# PCBMINI3.net
KiCad netlist of a schematic drawn in EAGLE
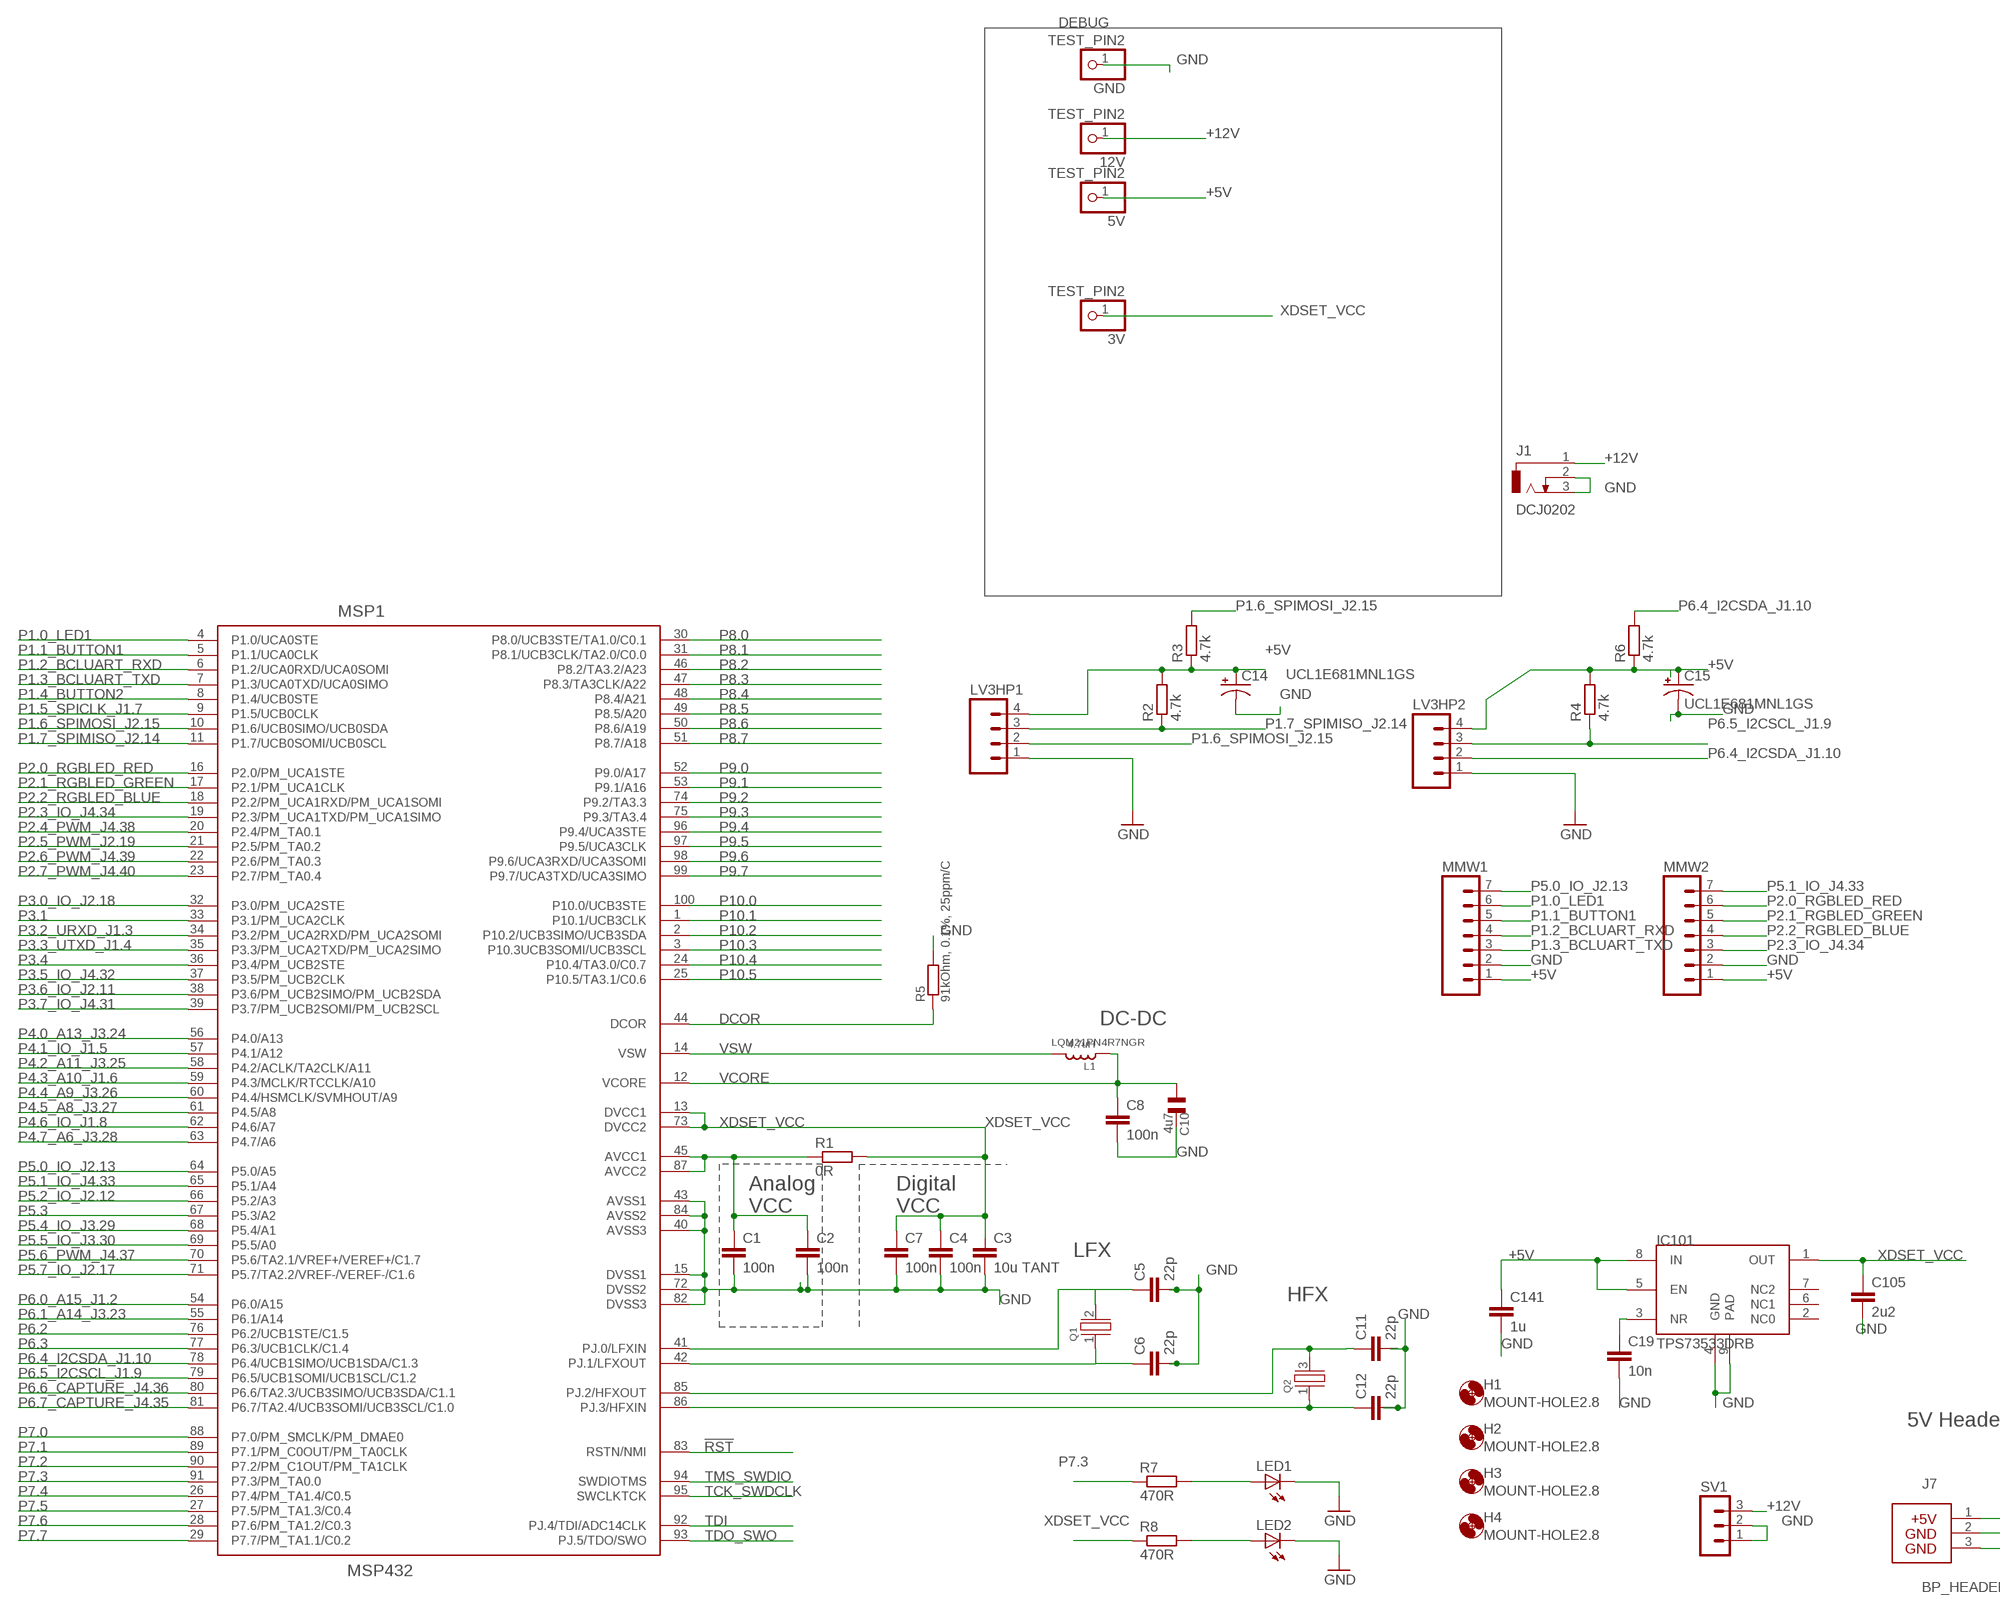
[diagram p0: schematic, sheet 1, part 1 of 2]
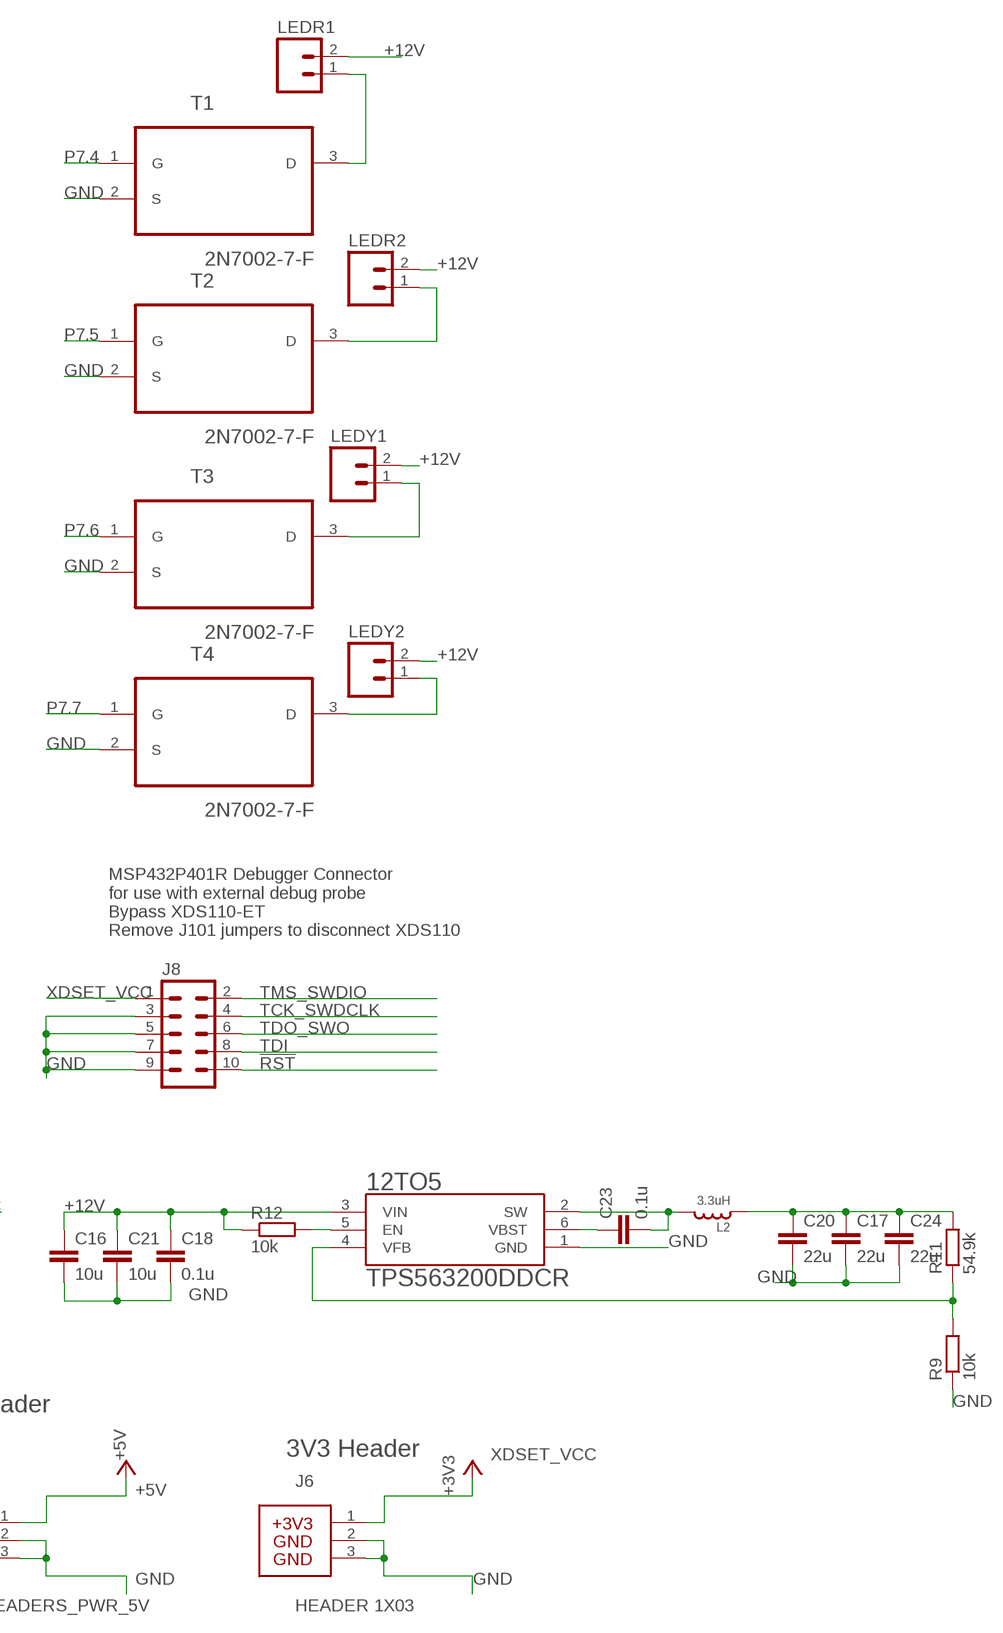
[diagram p1: schematic, sheet 1, part 2 of 2]

(export (version "E")
  (design (tool "Eeschema 10.0.6"))
  (components
    (comp (ref "3V")
      (value "TEST_PIN2")
      (footprint "eagle-import:1X01")
      (libsource (lib "eagle-import") (part "PINHD-1X1"))
    )
    (comp (ref "5V")
      (value "TEST_PIN2")
      (footprint "eagle-import:1X01")
      (libsource (lib "eagle-import") (part "PINHD-1X1"))
    )
    (comp (ref "12TO5")
      (value "TPS563200DDCR")
      (footprint "eagle-import:SOT95P280X110-6N")
      (fields (field (name "MF") "Texas Instruments"))
      (libsource (lib "eagle-import") (part "TPS563200DDCR"))
    )
    (comp (ref "12V")
      (value "TEST_PIN2")
      (footprint "eagle-import:1X01")
      (libsource (lib "eagle-import") (part "PINHD-1X1"))
    )
    (comp (ref "C1")
      (value "100n")
      (footprint "eagle-import:C0805")
      (libsource (lib "eagle-import") (part "C"))
    )
    (comp (ref "C2")
      (value "100n")
      (footprint "eagle-import:C0805")
      (libsource (lib "eagle-import") (part "C"))
    )
    (comp (ref "C3")
      (value "10u TANT")
      (footprint "eagle-import:C0805")
      (libsource (lib "eagle-import") (part "C"))
    )
    (comp (ref "C4")
      (value "100n")
      (footprint "eagle-import:C0805")
      (libsource (lib "eagle-import") (part "C"))
    )
    (comp (ref "C5")
      (value "22p")
      (footprint "eagle-import:C0805")
      (libsource (lib "eagle-import") (part "C"))
    )
    (comp (ref "C6")
      (value "22p")
      (footprint "eagle-import:C0805")
      (libsource (lib "eagle-import") (part "C"))
    )
    (comp (ref "C7")
      (value "100n")
      (footprint "eagle-import:C0805")
      (libsource (lib "eagle-import") (part "C"))
    )
    (comp (ref "C8")
      (value "100n")
      (footprint "eagle-import:C0805")
      (libsource (lib "eagle-import") (part "C"))
    )
    (comp (ref "C10")
      (value "4u7")
      (footprint "eagle-import:CSMD0805")
      (libsource (lib "eagle-import") (part "CSMD0805"))
    )
    (comp (ref "C11")
      (value "22p")
      (footprint "eagle-import:C0805")
      (libsource (lib "eagle-import") (part "C"))
    )
    (comp (ref "C12")
      (value "22p")
      (footprint "eagle-import:C0805")
      (libsource (lib "eagle-import") (part "C"))
    )
    (comp (ref "C14")
      (value "UCL1E681MNL1GS")
      (footprint "eagle-import:CAPAE1030X1350N")
      (fields (field (name "MF") "Nichicon"))
      (libsource (lib "eagle-import") (part "UCL1E681MNL1GS"))
    )
    (comp (ref "C15")
      (value "UCL1E681MNL1GS")
      (footprint "eagle-import:CAPAE1030X1350N")
      (fields (field (name "MF") "Nichicon"))
      (libsource (lib "eagle-import") (part "UCL1E681MNL1GS"))
    )
    (comp (ref "C16")
      (value "10u")
      (footprint "eagle-import:C0805")
      (libsource (lib "eagle-import") (part "C"))
    )
    (comp (ref "C17")
      (value "22u")
      (footprint "eagle-import:C0805")
      (libsource (lib "eagle-import") (part "C"))
    )
    (comp (ref "C18")
      (value "0.1u")
      (footprint "eagle-import:C0805")
      (libsource (lib "eagle-import") (part "C"))
    )
    (comp (ref "C19")
      (value "10n")
      (footprint "eagle-import:C0603")
      (libsource (lib "eagle-import") (part "C-EUC0603"))
    )
    (comp (ref "C20")
      (value "22u")
      (footprint "eagle-import:C0805")
      (libsource (lib "eagle-import") (part "C"))
    )
    (comp (ref "C21")
      (value "10u")
      (footprint "eagle-import:C0805")
      (libsource (lib "eagle-import") (part "C"))
    )
    (comp (ref "C23")
      (value "0.1u")
      (footprint "eagle-import:C0805")
      (libsource (lib "eagle-import") (part "C"))
    )
    (comp (ref "C24")
      (value "22u")
      (footprint "eagle-import:C0805")
      (libsource (lib "eagle-import") (part "C"))
    )
    (comp (ref "C105")
      (value "2u2")
      (footprint "eagle-import:C0603")
      (libsource (lib "eagle-import") (part "C-EUC0603"))
    )
    (comp (ref "C141")
      (value "1u")
      (footprint "eagle-import:C0603")
      (libsource (lib "eagle-import") (part "C-EUC0603"))
    )
    (comp (ref "GND")
      (value "TEST_PIN2")
      (footprint "eagle-import:1X01")
      (libsource (lib "eagle-import") (part "PINHD-1X1"))
    )
    (comp (ref "H1")
      (value "MOUNT-HOLE2.8")
      (footprint "eagle-import:2,8")
      (libsource (lib "eagle-import") (part "MOUNT-HOLE2.8"))
    )
    (comp (ref "H2")
      (value "MOUNT-HOLE2.8")
      (footprint "eagle-import:2,8")
      (libsource (lib "eagle-import") (part "MOUNT-HOLE2.8"))
    )
    (comp (ref "H3")
      (value "MOUNT-HOLE2.8")
      (footprint "eagle-import:2,8")
      (libsource (lib "eagle-import") (part "MOUNT-HOLE2.8"))
    )
    (comp (ref "H4")
      (value "MOUNT-HOLE2.8")
      (footprint "eagle-import:2,8")
      (libsource (lib "eagle-import") (part "MOUNT-HOLE2.8"))
    )
    (comp (ref "IC101")
      (value "TPS73533DRB")
      (footprint "eagle-import:SON8")
      (libsource (lib "eagle-import") (part "TPS73633DRB"))
    )
    (comp (ref "J1")
      (value "DCJ0202")
      (footprint "eagle-import:DCJ0202")
      (libsource (lib "eagle-import") (part "DCJ0202"))
    )
    (comp (ref "J6")
      (value "HEADER 1X03")
      (footprint "eagle-import:3PIN_PWR_3V3")
      (libsource (lib "eagle-import") (part "BP_HEADERS_PWR_3V3-TH100"))
    )
    (comp (ref "J7")
      (value "BP_HEADERS_PWR_5V")
      (footprint "eagle-import:3PIN_PWR_5V")
      (libsource (lib "eagle-import") (part "BP_HEADERS_PWR_5V"))
    )
    (comp (ref "J8")
      (value "DEBUG_ARM-10")
      (footprint "eagle-import:ARM-10")
      (libsource (lib "eagle-import") (part "DEBUG_ARM-10"))
    )
    (comp (ref "L1")
      (value "4.7uH")
      (footprint "eagle-import:0806")
      (libsource (lib "eagle-import") (part "LQM2MP_G0"))
    )
    (comp (ref "L2")
      (value "3.3uH")
      (footprint "eagle-import:0806")
      (libsource (lib "eagle-import") (part "LQM2MP_G0"))
    )
    (comp (ref "LED1")
      (value "LED_E")
      (footprint "eagle-import:LED_1206")
      (libsource (lib "eagle-import") (part "LED_E"))
    )
    (comp (ref "LED2")
      (value "LED_E")
      (footprint "eagle-import:LED_1206")
      (libsource (lib "eagle-import") (part "LED_E"))
    )
    (comp (ref "LEDR1")
      (value "MA02")
      (footprint "eagle-import:02PA")
      (libsource (lib "eagle-import") (part "MA02"))
    )
    (comp (ref "LEDR2")
      (value "MA02")
      (footprint "eagle-import:02PA")
      (libsource (lib "eagle-import") (part "MA02"))
    )
    (comp (ref "LEDY1")
      (value "MA02")
      (footprint "eagle-import:02PA")
      (libsource (lib "eagle-import") (part "MA02"))
    )
    (comp (ref "LEDY2")
      (value "MA02")
      (footprint "eagle-import:02PA")
      (libsource (lib "eagle-import") (part "MA02"))
    )
    (comp (ref "LV3HP1")
      (value "MA04")
      (footprint "eagle-import:04PA")
      (libsource (lib "eagle-import") (part "MA04"))
    )
    (comp (ref "LV3HP2")
      (value "MA04")
      (footprint "eagle-import:04PA")
      (libsource (lib "eagle-import") (part "MA04"))
    )
    (comp (ref "MMW1")
      (value "MA07")
      (footprint "eagle-import:07PA")
      (libsource (lib "eagle-import") (part "MA07"))
    )
    (comp (ref "MMW2")
      (value "MA07")
      (footprint "eagle-import:07PA")
      (libsource (lib "eagle-import") (part "MA07"))
    )
    (comp (ref "MSP1")
      (value "MSP432")
      (footprint "eagle-import:PZ100")
      (libsource (lib "eagle-import") (part "MSP432"))
    )
    (comp (ref "Q1")
      (value "CRYSTALLF_GENERAL")
      (footprint "eagle-import:LF_XTAL")
      (libsource (lib "eagle-import") (part "CRYSTALLF_GENERAL"))
    )
    (comp (ref "Q2")
      (value "CRYSTALEPSON_FA-238")
      (footprint "eagle-import:FA-238")
      (libsource (lib "eagle-import") (part "CRYSTALEPSON_FA-238"))
    )
    (comp (ref "R1")
      (value "0R")
      (footprint "eagle-import:R0805")
      (libsource (lib "eagle-import") (part "R"))
    )
    (comp (ref "R2")
      (value "4.7k")
      (footprint "eagle-import:R0805")
      (libsource (lib "eagle-import") (part "R"))
    )
    (comp (ref "R3")
      (value "4.7k")
      (footprint "eagle-import:R0805")
      (libsource (lib "eagle-import") (part "R"))
    )
    (comp (ref "R4")
      (value "4.7k")
      (footprint "eagle-import:R0805")
      (libsource (lib "eagle-import") (part "R"))
    )
    (comp (ref "R5")
      (value "91kOhm, 0.1%, 25ppm/C")
      (footprint "eagle-import:0805")
      (libsource (lib "eagle-import") (part "R_0805"))
    )
    (comp (ref "R6")
      (value "4.7k")
      (footprint "eagle-import:R0805")
      (libsource (lib "eagle-import") (part "R"))
    )
    (comp (ref "R7")
      (value "470R")
      (footprint "eagle-import:R0805")
      (libsource (lib "eagle-import") (part "R"))
    )
    (comp (ref "R8")
      (value "470R")
      (footprint "eagle-import:R0805")
      (libsource (lib "eagle-import") (part "R"))
    )
    (comp (ref "R9")
      (value "10k")
      (footprint "eagle-import:R0805")
      (libsource (lib "eagle-import") (part "R"))
    )
    (comp (ref "R11")
      (value "54.9k")
      (footprint "eagle-import:R0805")
      (libsource (lib "eagle-import") (part "R"))
    )
    (comp (ref "R12")
      (value "10k")
      (footprint "eagle-import:R0805")
      (libsource (lib "eagle-import") (part "R"))
    )
    (comp (ref "SV1")
      (value "MA03-1")
      (footprint "eagle-import:MA03-1")
      (libsource (lib "eagle-import") (part "MA03-1"))
    )
    (comp (ref "T1")
      (value "2N7002-7-F")
      (footprint "eagle-import:SOT103P240X110-3N")
      (fields (field (name "MF") "Diodes Inc."))
      (libsource (lib "eagle-import") (part "2N7002-7-F"))
    )
    (comp (ref "T2")
      (value "2N7002-7-F")
      (footprint "eagle-import:SOT103P240X110-3N")
      (fields (field (name "MF") "Diodes Inc."))
      (libsource (lib "eagle-import") (part "2N7002-7-F"))
    )
    (comp (ref "T3")
      (value "2N7002-7-F")
      (footprint "eagle-import:SOT103P240X110-3N")
      (fields (field (name "MF") "Diodes Inc."))
      (libsource (lib "eagle-import") (part "2N7002-7-F"))
    )
    (comp (ref "T4")
      (value "2N7002-7-F")
      (footprint "eagle-import:SOT103P240X110-3N")
      (fields (field (name "MF") "Diodes Inc."))
      (libsource (lib "eagle-import") (part "2N7002-7-F"))
    )
  )
  (nets
    (net (code "1") (name "+3V3") (class "Default")
      (node (ref "3V") (pin "1") (pinfunction "1_1") (pintype "passive"))
      (node (ref "C105") (pin "1") (pinfunction "1_1") (pintype "passive"))
      (node (ref "C3") (pin "1") (pinfunction "1_1") (pintype "passive"))
      (node (ref "C4") (pin "1") (pinfunction "1_1") (pintype "passive"))
      (node (ref "C7") (pin "1") (pinfunction "1_1") (pintype "passive"))
      (node (ref "IC101") (pin "1") (pinfunction "OUT_1") (pintype "bidirectional"))
      (node (ref "J6") (pin "1") (pinfunction "1_1") (pintype "bidirectional"))
      (node (ref "J8") (pin "1") (pinfunction "1_1") (pintype "passive"))
      (node (ref "MSP1") (pin "13") (pinfunction "DVCC1_13") (pintype "power_in"))
      (node (ref "MSP1") (pin "73") (pinfunction "DVCC2_73") (pintype "power_in"))
      (node (ref "R1") (pin "2") (pinfunction "2_2") (pintype "passive"))
      (node (ref "R8") (pin "1") (pinfunction "1_1") (pintype "passive"))
    )
    (net (code "2") (name "+5V") (class "Default")
      (node (ref "5V") (pin "1") (pinfunction "1_1") (pintype "passive"))
      (node (ref "C14") (pin "A") (pinfunction "+_A") (pintype "passive"))
      (node (ref "C141") (pin "1") (pinfunction "1_1") (pintype "passive"))
      (node (ref "C15") (pin "A") (pinfunction "+_A") (pintype "passive"))
      (node (ref "IC101") (pin "5") (pinfunction "EN_5") (pintype "bidirectional"))
      (node (ref "IC101") (pin "8") (pinfunction "IN_8") (pintype "bidirectional"))
      (node (ref "J7") (pin "1") (pinfunction "1_1") (pintype "bidirectional"))
      (node (ref "LV3HP1") (pin "4") (pinfunction "4_4") (pintype "passive"))
      (node (ref "LV3HP2") (pin "4") (pinfunction "4_4") (pintype "passive"))
      (node (ref "MMW1") (pin "1") (pinfunction "1_1") (pintype "passive"))
      (node (ref "MMW2") (pin "1") (pinfunction "1_1") (pintype "passive"))
      (node (ref "R2") (pin "2") (pinfunction "2_2") (pintype "passive"))
      (node (ref "R3") (pin "1") (pinfunction "1_1") (pintype "passive"))
      (node (ref "R4") (pin "2") (pinfunction "2_2") (pintype "passive"))
      (node (ref "R6") (pin "1") (pinfunction "1_1") (pintype "passive"))
    )
    (net (code "3") (name "/+12V") (class "Default")
      (node (ref "12TO5") (pin "3") (pinfunction "VIN_3") (pintype "input"))
      (node (ref "12V") (pin "1") (pinfunction "1_1") (pintype "passive"))
      (node (ref "C16") (pin "1") (pinfunction "1_1") (pintype "passive"))
      (node (ref "C18") (pin "1") (pinfunction "1_1") (pintype "passive"))
      (node (ref "C21") (pin "1") (pinfunction "1_1") (pintype "passive"))
      (node (ref "J1") (pin "1") (pinfunction "1_1") (pintype "passive"))
      (node (ref "LEDR1") (pin "2") (pinfunction "2_2") (pintype "passive"))
      (node (ref "LEDR2") (pin "2") (pinfunction "2_2") (pintype "passive"))
      (node (ref "LEDY1") (pin "2") (pinfunction "2_2") (pintype "passive"))
      (node (ref "LEDY2") (pin "2") (pinfunction "2_2") (pintype "passive"))
      (node (ref "R12") (pin "1") (pinfunction "1_1") (pintype "passive"))
      (node (ref "SV1") (pin "3") (pinfunction "3_3") (pintype "passive"))
    )
    (net (code "4") (name "/DCOR") (class "Default")
      (node (ref "MSP1") (pin "44") (pinfunction "DCOR_44") (pintype "power_in"))
      (node (ref "R5") (pin "1") (pinfunction "1_1") (pintype "passive"))
    )
    (net (code "5") (name "/P1.0_LED1") (class "Default")
      (node (ref "MMW1") (pin "6") (pinfunction "6_6") (pintype "passive"))
      (node (ref "MSP1") (pin "4") (pinfunction "P1.0/UCA0STE_4") (pintype "power_in"))
    )
    (net (code "6") (name "/P1.1_BUTTON1") (class "Default")
      (node (ref "MMW1") (pin "5") (pinfunction "5_5") (pintype "passive"))
      (node (ref "MSP1") (pin "5") (pinfunction "P1.1/UCA0CLK_5") (pintype "power_in"))
    )
    (net (code "7") (name "/P1.2_BCLUART_RXD") (class "Default")
      (node (ref "MMW1") (pin "4") (pinfunction "4_4") (pintype "passive"))
      (node (ref "MSP1") (pin "6") (pinfunction "P1.2/UCA0RXD/UCA0SOMI_6") (pintype "power_in"))
    )
    (net (code "8") (name "/P1.3_BCLUART_TXD") (class "Default")
      (node (ref "MMW1") (pin "3") (pinfunction "3_3") (pintype "passive"))
      (node (ref "MSP1") (pin "7") (pinfunction "P1.3/UCA0TXD/UCA0SIMO_7") (pintype "power_in"))
    )
    (net (code "9") (name "/P1.4_BUTTON2") (class "Default")
      (node (ref "MSP1") (pin "8") (pinfunction "P1.4/UCB0STE_8") (pintype "power_in"))
    )
    (net (code "10") (name "/P1.5_SPICLK_J1.7") (class "Default")
      (node (ref "MSP1") (pin "9") (pinfunction "P1.5/UCB0CLK_9") (pintype "power_in"))
    )
    (net (code "11") (name "/P1.6_SPIMOSI_J2.15") (class "Default")
      (node (ref "LV3HP1") (pin "2") (pinfunction "2_2") (pintype "passive"))
      (node (ref "MSP1") (pin "10") (pinfunction "P1.6/UCB0SIMO/UCB0SDA_10") (pintype "power_in"))
      (node (ref "R3") (pin "2") (pinfunction "2_2") (pintype "passive"))
    )
    (net (code "12") (name "/P1.7_SPIMISO_J2.14") (class "Default")
      (node (ref "LV3HP1") (pin "3") (pinfunction "3_3") (pintype "passive"))
      (node (ref "MSP1") (pin "11") (pinfunction "P1.7/UCB0SOMI/UCB0SCL_11") (pintype "power_in"))
      (node (ref "R2") (pin "1") (pinfunction "1_1") (pintype "passive"))
    )
    (net (code "13") (name "/P2.0_RGBLED_RED") (class "Default")
      (node (ref "MMW2") (pin "6") (pinfunction "6_6") (pintype "passive"))
      (node (ref "MSP1") (pin "16") (pinfunction "P2.0/PM_UCA1STE_16") (pintype "power_in"))
    )
    (net (code "14") (name "/P2.1_RGBLED_GREEN") (class "Default")
      (node (ref "MMW2") (pin "5") (pinfunction "5_5") (pintype "passive"))
      (node (ref "MSP1") (pin "17") (pinfunction "P2.1/PM_UCA1CLK_17") (pintype "power_in"))
    )
    (net (code "15") (name "/P2.2_RGBLED_BLUE") (class "Default")
      (node (ref "MMW2") (pin "4") (pinfunction "4_4") (pintype "passive"))
      (node (ref "MSP1") (pin "18") (pinfunction "P2.2/PM_UCA1RXD/PM_UCA1SOMI_18") (pintype "power_in"))
    )
    (net (code "16") (name "/P2.3_IO_J4.34") (class "Default")
      (node (ref "MMW2") (pin "3") (pinfunction "3_3") (pintype "passive"))
      (node (ref "MSP1") (pin "19") (pinfunction "P2.3/PM_UCA1TXD/PM_UCA1SIMO_19") (pintype "power_in"))
    )
    (net (code "17") (name "/P2.4_PWM_J4.38") (class "Default")
      (node (ref "MSP1") (pin "20") (pinfunction "P2.4/PM_TA0.1_20") (pintype "power_in"))
    )
    (net (code "18") (name "/P2.5_PWM_J2.19") (class "Default")
      (node (ref "MSP1") (pin "21") (pinfunction "P2.5/PM_TA0.2_21") (pintype "power_in"))
    )
    (net (code "19") (name "/P2.6_PWM_J4.39") (class "Default")
      (node (ref "MSP1") (pin "22") (pinfunction "P2.6/PM_TA0.3_22") (pintype "power_in"))
    )
    (net (code "20") (name "/P2.7_PWM_J4.40") (class "Default")
      (node (ref "MSP1") (pin "23") (pinfunction "P2.7/PM_TA0.4_23") (pintype "power_in"))
    )
    (net (code "21") (name "/P3.0_IO_J2.18") (class "Default")
      (node (ref "MSP1") (pin "32") (pinfunction "P3.0/PM_UCA2STE_32") (pintype "power_in"))
    )
    (net (code "22") (name "/P3.1") (class "Default")
      (node (ref "MSP1") (pin "33") (pinfunction "P3.1/PM_UCA2CLK_33") (pintype "power_in"))
    )
    (net (code "23") (name "/P3.2_URXD_J1.3") (class "Default")
      (node (ref "MSP1") (pin "34") (pinfunction "P3.2/PM_UCA2RXD/PM_UCA2SOMI_34") (pintype "power_in"))
    )
    (net (code "24") (name "/P3.3_UTXD_J1.4") (class "Default")
      (node (ref "MSP1") (pin "35") (pinfunction "P3.3/PM_UCA2TXD/PM_UCA2SIMO_35") (pintype "power_in"))
    )
    (net (code "25") (name "/P3.4") (class "Default")
      (node (ref "MSP1") (pin "36") (pinfunction "P3.4/PM_UCB2STE_36") (pintype "power_in"))
    )
    (net (code "26") (name "/P3.5_IO_J4.32") (class "Default")
      (node (ref "MSP1") (pin "37") (pinfunction "P3.5/PM_UCB2CLK_37") (pintype "power_in"))
    )
    (net (code "27") (name "/P3.6_IO_J2.11") (class "Default")
      (node (ref "MSP1") (pin "38") (pinfunction "P3.6/PM_UCB2SIMO/PM_UCB2SDA_38") (pintype "power_in"))
    )
    (net (code "28") (name "/P3.7_IO_J4.31") (class "Default")
      (node (ref "MSP1") (pin "39") (pinfunction "P3.7/PM_UCB2SOMI/PM_UCB2SCL_39") (pintype "power_in"))
    )
    (net (code "29") (name "/P4.0_A13_J3.24") (class "Default")
      (node (ref "MSP1") (pin "56") (pinfunction "P4.0/A13_56") (pintype "power_in"))
    )
    (net (code "30") (name "/P4.1_IO_J1.5") (class "Default")
      (node (ref "MSP1") (pin "57") (pinfunction "P4.1/A12_57") (pintype "power_in"))
    )
    (net (code "31") (name "/P4.2_A11_J3.25") (class "Default")
      (node (ref "MSP1") (pin "58") (pinfunction "P4.2/ACLK/TA2CLK/A11_58") (pintype "power_in"))
    )
    (net (code "32") (name "/P4.3_A10_J1.6") (class "Default")
      (node (ref "MSP1") (pin "59") (pinfunction "P4.3/MCLK/RTCCLK/A10_59") (pintype "power_in"))
    )
    (net (code "33") (name "/P4.4_A9_J3.26") (class "Default")
      (node (ref "MSP1") (pin "60") (pinfunction "P4.4/HSMCLK/SVMHOUT/A9_60") (pintype "power_in"))
    )
    (net (code "34") (name "/P4.5_A8_J3.27") (class "Default")
      (node (ref "MSP1") (pin "61") (pinfunction "P4.5/A8_61") (pintype "power_in"))
    )
    (net (code "35") (name "/P4.6_IO_J1.8") (class "Default")
      (node (ref "MSP1") (pin "62") (pinfunction "P4.6/A7_62") (pintype "power_in"))
    )
    (net (code "36") (name "/P4.7_A6_J3.28") (class "Default")
      (node (ref "MSP1") (pin "63") (pinfunction "P4.7/A6_63") (pintype "power_in"))
    )
    (net (code "37") (name "/P5.0_IO_J2.13") (class "Default")
      (node (ref "MMW1") (pin "7") (pinfunction "7_7") (pintype "passive"))
      (node (ref "MSP1") (pin "64") (pinfunction "P5.0/A5_64") (pintype "power_in"))
    )
    (net (code "38") (name "/P5.1_IO_J4.33") (class "Default")
      (node (ref "MMW2") (pin "7") (pinfunction "7_7") (pintype "passive"))
      (node (ref "MSP1") (pin "65") (pinfunction "P5.1/A4_65") (pintype "power_in"))
    )
    (net (code "39") (name "/P5.2_IO_J2.12") (class "Default")
      (node (ref "MSP1") (pin "66") (pinfunction "P5.2/A3_66") (pintype "power_in"))
    )
    (net (code "40") (name "/P5.3") (class "Default")
      (node (ref "MSP1") (pin "67") (pinfunction "P5.3/A2_67") (pintype "power_in"))
    )
    (net (code "41") (name "/P5.4_IO_J3.29") (class "Default")
      (node (ref "MSP1") (pin "68") (pinfunction "P5.4/A1_68") (pintype "power_in"))
    )
    (net (code "42") (name "/P5.5_IO_J3.30") (class "Default")
      (node (ref "MSP1") (pin "69") (pinfunction "P5.5/A0_69") (pintype "power_in"))
    )
    (net (code "43") (name "/P5.6_PWM_J4.37") (class "Default")
      (node (ref "MSP1") (pin "70") (pinfunction "P5.6/TA2.1/VREF+/VEREF+/C1.7_70") (pintype "power_in"))
    )
    (net (code "44") (name "/P5.7_IO_J2.17") (class "Default")
      (node (ref "MSP1") (pin "71") (pinfunction "P5.7/TA2.2/VREF-/VEREF-/C1.6_71") (pintype "power_in"))
    )
    (net (code "45") (name "/P6.0_A15_J1.2") (class "Default")
      (node (ref "MSP1") (pin "54") (pinfunction "P6.0/A15_54") (pintype "power_in"))
    )
    (net (code "46") (name "/P6.1_A14_J3.23") (class "Default")
      (node (ref "MSP1") (pin "55") (pinfunction "P6.1/A14_55") (pintype "power_in"))
    )
    (net (code "47") (name "/P6.2") (class "Default")
      (node (ref "MSP1") (pin "76") (pinfunction "P6.2/UCB1STE/C1.5_76") (pintype "power_in"))
    )
    (net (code "48") (name "/P6.3") (class "Default")
      (node (ref "MSP1") (pin "77") (pinfunction "P6.3/UCB1CLK/C1.4_77") (pintype "power_in"))
    )
    (net (code "49") (name "/P6.4_I2CSDA_J1.10") (class "Default")
      (node (ref "LV3HP2") (pin "2") (pinfunction "2_2") (pintype "passive"))
      (node (ref "MSP1") (pin "78") (pinfunction "P6.4/UCB1SIMO/UCB1SDA/C1.3_78") (pintype "power_in"))
      (node (ref "R6") (pin "2") (pinfunction "2_2") (pintype "passive"))
    )
    (net (code "50") (name "/P6.5_I2CSCL_J1.9") (class "Default")
      (node (ref "LV3HP2") (pin "3") (pinfunction "3_3") (pintype "passive"))
      (node (ref "MSP1") (pin "79") (pinfunction "P6.5/UCB1SOMI/UCB1SCL/C1.2_79") (pintype "power_in"))
      (node (ref "R4") (pin "1") (pinfunction "1_1") (pintype "passive"))
    )
    (net (code "51") (name "/P6.6_CAPTURE_J4.36") (class "Default")
      (node (ref "MSP1") (pin "80") (pinfunction "P6.6/TA2.3/UCB3SIMO/UCB3SDA/C1.1_80") (pintype "power_in"))
    )
    (net (code "52") (name "/P6.7_CAPTURE_J4.35") (class "Default")
      (node (ref "MSP1") (pin "81") (pinfunction "P6.7/TA2.4/UCB3SOMI/UCB3SCL/C1.0_81") (pintype "power_in"))
    )
    (net (code "53") (name "/P7.0") (class "Default")
      (node (ref "MSP1") (pin "88") (pinfunction "P7.0/PM_SMCLK/PM_DMAE0_88") (pintype "power_in"))
    )
    (net (code "54") (name "/P7.1") (class "Default")
      (node (ref "MSP1") (pin "89") (pinfunction "P7.1/PM_C0OUT/PM_TA0CLK_89") (pintype "power_in"))
    )
    (net (code "55") (name "/P7.2") (class "Default")
      (node (ref "MSP1") (pin "90") (pinfunction "P7.2/PM_C1OUT/PM_TA1CLK_90") (pintype "power_in"))
    )
    (net (code "56") (name "/P7.3") (class "Default")
      (node (ref "MSP1") (pin "91") (pinfunction "P7.3/PM_TA0.0_91") (pintype "power_in"))
      (node (ref "R7") (pin "1") (pinfunction "1_1") (pintype "passive"))
    )
    (net (code "57") (name "/P7.4") (class "Default")
      (node (ref "MSP1") (pin "26") (pinfunction "P7.4/PM_TA1.4/C0.5_26") (pintype "power_in"))
      (node (ref "T1") (pin "1") (pinfunction "G_1") (pintype "input"))
    )
    (net (code "58") (name "/P7.5") (class "Default")
      (node (ref "MSP1") (pin "27") (pinfunction "P7.5/PM_TA1.3/C0.4_27") (pintype "power_in"))
      (node (ref "T2") (pin "1") (pinfunction "G_1") (pintype "input"))
    )
    (net (code "59") (name "/P7.6") (class "Default")
      (node (ref "MSP1") (pin "28") (pinfunction "P7.6/PM_TA1.2/C0.3_28") (pintype "power_in"))
      (node (ref "T3") (pin "1") (pinfunction "G_1") (pintype "input"))
    )
    (net (code "60") (name "/P7.7") (class "Default")
      (node (ref "MSP1") (pin "29") (pinfunction "P7.7/PM_TA1.1/C0.2_29") (pintype "power_in"))
      (node (ref "T4") (pin "1") (pinfunction "G_1") (pintype "input"))
    )
    (net (code "61") (name "/P8.0") (class "Default")
      (node (ref "MSP1") (pin "30") (pinfunction "P8.0/UCB3STE/TA1.0/C0.1_30") (pintype "power_in"))
    )
    (net (code "62") (name "/P8.1") (class "Default")
      (node (ref "MSP1") (pin "31") (pinfunction "P8.1/UCB3CLK/TA2.0/C0.0_31") (pintype "power_in"))
    )
    (net (code "63") (name "/P8.2") (class "Default")
      (node (ref "MSP1") (pin "46") (pinfunction "P8.2/TA3.2/A23_46") (pintype "power_in"))
    )
    (net (code "64") (name "/P8.3") (class "Default")
      (node (ref "MSP1") (pin "47") (pinfunction "P8.3/TA3CLK/A22_47") (pintype "power_in"))
    )
    (net (code "65") (name "/P8.4") (class "Default")
      (node (ref "MSP1") (pin "48") (pinfunction "P8.4/A21_48") (pintype "power_in"))
    )
    (net (code "66") (name "/P8.5") (class "Default")
      (node (ref "MSP1") (pin "49") (pinfunction "P8.5/A20_49") (pintype "power_in"))
    )
    (net (code "67") (name "/P8.6") (class "Default")
      (node (ref "MSP1") (pin "50") (pinfunction "P8.6/A19_50") (pintype "power_in"))
    )
    (net (code "68") (name "/P8.7") (class "Default")
      (node (ref "MSP1") (pin "51") (pinfunction "P8.7/A18_51") (pintype "power_in"))
    )
    (net (code "69") (name "/P9.0") (class "Default")
      (node (ref "MSP1") (pin "52") (pinfunction "P9.0/A17_52") (pintype "power_in"))
    )
    (net (code "70") (name "/P9.1") (class "Default")
      (node (ref "MSP1") (pin "53") (pinfunction "P9.1/A16_53") (pintype "power_in"))
    )
    (net (code "71") (name "/P9.2") (class "Default")
      (node (ref "MSP1") (pin "74") (pinfunction "P9.2/TA3.3_74") (pintype "power_in"))
    )
    (net (code "72") (name "/P9.3") (class "Default")
      (node (ref "MSP1") (pin "75") (pinfunction "P9.3/TA3.4_75") (pintype "power_in"))
    )
    (net (code "73") (name "/P9.4") (class "Default")
      (node (ref "MSP1") (pin "96") (pinfunction "P9.4/UCA3STE_96") (pintype "power_in"))
    )
    (net (code "74") (name "/P9.5") (class "Default")
      (node (ref "MSP1") (pin "97") (pinfunction "P9.5/UCA3CLK_97") (pintype "power_in"))
    )
    (net (code "75") (name "/P9.6") (class "Default")
      (node (ref "MSP1") (pin "98") (pinfunction "P9.6/UCA3RXD/UCA3SOMI_98") (pintype "power_in"))
    )
    (net (code "76") (name "/P9.7") (class "Default")
      (node (ref "MSP1") (pin "99") (pinfunction "P9.7/UCA3TXD/UCA3SIMO_99") (pintype "power_in"))
    )
    (net (code "77") (name "/P10.0") (class "Default")
      (node (ref "MSP1") (pin "100") (pinfunction "P10.0/UCB3STE_100") (pintype "power_in"))
    )
    (net (code "78") (name "/P10.1") (class "Default")
      (node (ref "MSP1") (pin "1") (pinfunction "P10.1/UCB3CLK_1") (pintype "power_in"))
    )
    (net (code "79") (name "/P10.2") (class "Default")
      (node (ref "MSP1") (pin "2") (pinfunction "P10.2/UCB3SIMO/UCB3SDA_2") (pintype "power_in"))
    )
    (net (code "80") (name "/P10.3") (class "Default")
      (node (ref "MSP1") (pin "3") (pinfunction "P10.3UCB3SOMI/UCB3SCL_3") (pintype "power_in"))
    )
    (net (code "81") (name "/P10.4") (class "Default")
      (node (ref "MSP1") (pin "24") (pinfunction "P10.4/TA3.0/C0.7_24") (pintype "power_in"))
    )
    (net (code "82") (name "/P10.5") (class "Default")
      (node (ref "MSP1") (pin "25") (pinfunction "P10.5/TA3.1/C0.6_25") (pintype "power_in"))
    )
    (net (code "83") (name "/TCK_SWDCLK") (class "Default")
      (node (ref "J8") (pin "4") (pinfunction "4_4") (pintype "passive"))
      (node (ref "MSP1") (pin "95") (pinfunction "SWCLKTCK_95") (pintype "power_in"))
    )
    (net (code "84") (name "/TDI") (class "Default")
      (node (ref "J8") (pin "8") (pinfunction "8_8") (pintype "passive"))
      (node (ref "MSP1") (pin "92") (pinfunction "PJ.4/TDI/ADC14CLK_92") (pintype "power_in"))
    )
    (net (code "85") (name "/TDO_SWO") (class "Default")
      (node (ref "J8") (pin "6") (pinfunction "6_6") (pintype "passive"))
      (node (ref "MSP1") (pin "93") (pinfunction "PJ.5/TDO/SWO_93") (pintype "power_in"))
    )
    (net (code "86") (name "/TMS_SWDIO") (class "Default")
      (node (ref "J8") (pin "2") (pinfunction "2_2") (pintype "passive"))
      (node (ref "MSP1") (pin "94") (pinfunction "SWDIOTMS_94") (pintype "power_in"))
    )
    (net (code "87") (name "/VCORE") (class "Default")
      (node (ref "C10") (pin "1") (pinfunction "1_1") (pintype "passive"))
      (node (ref "C8") (pin "1") (pinfunction "1_1") (pintype "passive"))
      (node (ref "L1") (pin "1") (pinfunction "1_1") (pintype "passive"))
      (node (ref "MSP1") (pin "12") (pinfunction "VCORE_12") (pintype "power_in"))
    )
    (net (code "88") (name "/VSW") (class "Default")
      (node (ref "L1") (pin "2") (pinfunction "2_2") (pintype "passive"))
      (node (ref "MSP1") (pin "14") (pinfunction "VSW_14") (pintype "power_in"))
    )
    (net (code "89") (name "/~{RST}") (class "Default")
      (node (ref "J8") (pin "10") (pinfunction "10_10") (pintype "passive"))
      (node (ref "MSP1") (pin "83") (pinfunction "RSTN/NMI_83") (pintype "power_in"))
    )
    (net (code "90") (name "GND") (class "Default")
      (node (ref "12TO5") (pin "1") (pinfunction "GND_1") (pintype "power_in"))
      (node (ref "C1") (pin "2") (pinfunction "2_2") (pintype "passive"))
      (node (ref "C10") (pin "2") (pinfunction "2_2") (pintype "passive"))
      (node (ref "C105") (pin "2") (pinfunction "2_2") (pintype "passive"))
      (node (ref "C11") (pin "2") (pinfunction "2_2") (pintype "passive"))
      (node (ref "C12") (pin "2") (pinfunction "2_2") (pintype "passive"))
      (node (ref "C14") (pin "C") (pinfunction "-_C") (pintype "passive"))
      (node (ref "C141") (pin "2") (pinfunction "2_2") (pintype "passive"))
      (node (ref "C15") (pin "C") (pinfunction "-_C") (pintype "passive"))
      (node (ref "C16") (pin "2") (pinfunction "2_2") (pintype "passive"))
      (node (ref "C17") (pin "2") (pinfunction "2_2") (pintype "passive"))
      (node (ref "C18") (pin "2") (pinfunction "2_2") (pintype "passive"))
      (node (ref "C19") (pin "2") (pinfunction "2_2") (pintype "passive"))
      (node (ref "C2") (pin "2") (pinfunction "2_2") (pintype "passive"))
      (node (ref "C20") (pin "2") (pinfunction "2_2") (pintype "passive"))
      (node (ref "C21") (pin "2") (pinfunction "2_2") (pintype "passive"))
      (node (ref "C24") (pin "2") (pinfunction "2_2") (pintype "passive"))
      (node (ref "C3") (pin "2") (pinfunction "2_2") (pintype "passive"))
      (node (ref "C4") (pin "2") (pinfunction "2_2") (pintype "passive"))
      (node (ref "C5") (pin "2") (pinfunction "2_2") (pintype "passive"))
      (node (ref "C6") (pin "2") (pinfunction "2_2") (pintype "passive"))
      (node (ref "C7") (pin "2") (pinfunction "2_2") (pintype "passive"))
      (node (ref "C8") (pin "2") (pinfunction "2_2") (pintype "passive"))
      (node (ref "GND") (pin "1") (pinfunction "1_1") (pintype "passive"))
      (node (ref "IC101") (pin "4") (pinfunction "GND_4") (pintype "bidirectional"))
      (node (ref "IC101") (pin "9") (pinfunction "PAD_9") (pintype "bidirectional"))
      (node (ref "J1") (pin "2") (pinfunction "2_2") (pintype "passive"))
      (node (ref "J1") (pin "3") (pinfunction "3_3") (pintype "passive"))
      (node (ref "J6") (pin "2") (pinfunction "2_2") (pintype "bidirectional"))
      (node (ref "J6") (pin "3") (pinfunction "3_3") (pintype "bidirectional"))
      (node (ref "J7") (pin "2") (pinfunction "2_2") (pintype "bidirectional"))
      (node (ref "J7") (pin "3") (pinfunction "3_3") (pintype "bidirectional"))
      (node (ref "J8") (pin "3") (pinfunction "3_3") (pintype "passive"))
      (node (ref "J8") (pin "5") (pinfunction "5_5") (pintype "passive"))
      (node (ref "J8") (pin "7") (pinfunction "7_7") (pintype "passive"))
      (node (ref "J8") (pin "9") (pinfunction "9_9") (pintype "passive"))
      (node (ref "LED1") (pin "C") (pinfunction "C_C") (pintype "passive"))
      (node (ref "LED2") (pin "C") (pinfunction "C_C") (pintype "passive"))
      (node (ref "LV3HP1") (pin "1") (pinfunction "1_1") (pintype "passive"))
      (node (ref "LV3HP2") (pin "1") (pinfunction "1_1") (pintype "passive"))
      (node (ref "MMW1") (pin "2") (pinfunction "2_2") (pintype "passive"))
      (node (ref "MMW2") (pin "2") (pinfunction "2_2") (pintype "passive"))
      (node (ref "MSP1") (pin "15") (pinfunction "DVSS1_15") (pintype "power_in"))
      (node (ref "MSP1") (pin "40") (pinfunction "AVSS3_40") (pintype "power_in"))
      (node (ref "MSP1") (pin "43") (pinfunction "AVSS1_43") (pintype "power_in"))
      (node (ref "MSP1") (pin "72") (pinfunction "DVSS2_72") (pintype "power_in"))
      (node (ref "MSP1") (pin "82") (pinfunction "DVSS3_82") (pintype "power_in"))
      (node (ref "MSP1") (pin "84") (pinfunction "AVSS2_84") (pintype "power_in"))
      (node (ref "R5") (pin "2") (pinfunction "2_2") (pintype "passive"))
      (node (ref "R9") (pin "1") (pinfunction "1_1") (pintype "passive"))
      (node (ref "SV1") (pin "1") (pinfunction "1_1") (pintype "passive"))
      (node (ref "SV1") (pin "2") (pinfunction "2_2") (pintype "passive"))
      (node (ref "T1") (pin "2") (pinfunction "S_2") (pintype "passive"))
      (node (ref "T2") (pin "2") (pinfunction "S_2") (pintype "passive"))
      (node (ref "T3") (pin "2") (pinfunction "S_2") (pintype "passive"))
      (node (ref "T4") (pin "2") (pinfunction "S_2") (pintype "passive"))
    )
    (net (code "91") (name "Net-(12TO5-EN)") (class "Default")
      (node (ref "12TO5") (pin "5") (pinfunction "EN_5") (pintype "input"))
      (node (ref "R12") (pin "2") (pinfunction "2_2") (pintype "passive"))
    )
    (net (code "92") (name "Net-(12TO5-SW)") (class "Default")
      (node (ref "12TO5") (pin "2") (pinfunction "SW_2") (pintype "passive"))
      (node (ref "C23") (pin "2") (pinfunction "2_2") (pintype "passive"))
      (node (ref "L2") (pin "2") (pinfunction "2_2") (pintype "passive"))
    )
    (net (code "93") (name "Net-(12TO5-VBST)") (class "Default")
      (node (ref "12TO5") (pin "6") (pinfunction "VBST_6") (pintype "passive"))
      (node (ref "C23") (pin "1") (pinfunction "1_1") (pintype "passive"))
    )
    (net (code "94") (name "Net-(12TO5-VFB)") (class "Default")
      (node (ref "12TO5") (pin "4") (pinfunction "VFB_4") (pintype "input"))
      (node (ref "R11") (pin "1") (pinfunction "1_1") (pintype "passive"))
      (node (ref "R9") (pin "2") (pinfunction "2_2") (pintype "passive"))
    )
    (net (code "95") (name "Net-(C17-Pad1)") (class "Default")
      (node (ref "C17") (pin "1") (pinfunction "1_1") (pintype "passive"))
      (node (ref "C20") (pin "1") (pinfunction "1_1") (pintype "passive"))
      (node (ref "C24") (pin "1") (pinfunction "1_1") (pintype "passive"))
      (node (ref "L2") (pin "1") (pinfunction "1_1") (pintype "passive"))
      (node (ref "R11") (pin "2") (pinfunction "2_2") (pintype "passive"))
    )
    (net (code "96") (name "Net-(IC101-NR)") (class "Default")
      (node (ref "C19") (pin "1") (pinfunction "1_1") (pintype "passive"))
      (node (ref "IC101") (pin "3") (pinfunction "NR_3") (pintype "bidirectional"))
    )
    (net (code "97") (name "Net-(LED1-PadA)") (class "Default")
      (node (ref "LED1") (pin "A") (pinfunction "A_A") (pintype "passive"))
      (node (ref "R7") (pin "2") (pinfunction "2_2") (pintype "passive"))
    )
    (net (code "98") (name "Net-(LED2-PadA)") (class "Default")
      (node (ref "LED2") (pin "A") (pinfunction "A_A") (pintype "passive"))
      (node (ref "R8") (pin "2") (pinfunction "2_2") (pintype "passive"))
    )
    (net (code "99") (name "Net-(MSP1-AVCC1)") (class "Default")
      (node (ref "C1") (pin "1") (pinfunction "1_1") (pintype "passive"))
      (node (ref "C2") (pin "1") (pinfunction "1_1") (pintype "passive"))
      (node (ref "MSP1") (pin "45") (pinfunction "AVCC1_45") (pintype "power_in"))
      (node (ref "MSP1") (pin "87") (pinfunction "AVCC2_87") (pintype "power_in"))
      (node (ref "R1") (pin "1") (pinfunction "1_1") (pintype "passive"))
    )
    (net (code "100") (name "Net-(MSP1-PJ.0{slash}LFXIN)") (class "Default")
      (node (ref "C5") (pin "1") (pinfunction "1_1") (pintype "passive"))
      (node (ref "MSP1") (pin "41") (pinfunction "PJ.0/LFXIN_41") (pintype "power_in"))
      (node (ref "Q1") (pin "2") (pinfunction "2_2") (pintype "passive"))
    )
    (net (code "101") (name "Net-(MSP1-PJ.1{slash}LFXOUT)") (class "Default")
      (node (ref "C6") (pin "1") (pinfunction "1_1") (pintype "passive"))
      (node (ref "MSP1") (pin "42") (pinfunction "PJ.1/LFXOUT_42") (pintype "power_in"))
      (node (ref "Q1") (pin "1") (pinfunction "1_1") (pintype "passive"))
    )
    (net (code "102") (name "Net-(MSP1-PJ.2{slash}HFXOUT)") (class "Default")
      (node (ref "C11") (pin "1") (pinfunction "1_1") (pintype "passive"))
      (node (ref "MSP1") (pin "85") (pinfunction "PJ.2/HFXOUT_85") (pintype "power_in"))
      (node (ref "Q2") (pin "3") (pinfunction "2_3") (pintype "passive"))
    )
    (net (code "103") (name "Net-(MSP1-PJ.3{slash}HFXIN)") (class "Default")
      (node (ref "C12") (pin "1") (pinfunction "1_1") (pintype "passive"))
      (node (ref "MSP1") (pin "86") (pinfunction "PJ.3/HFXIN_86") (pintype "power_in"))
      (node (ref "Q2") (pin "1") (pinfunction "1_1") (pintype "passive"))
    )
    (net (code "104") (name "Net-(T1-D)") (class "Default")
      (node (ref "LEDR1") (pin "1") (pinfunction "1_1") (pintype "passive"))
      (node (ref "T1") (pin "3") (pinfunction "D_3") (pintype "output"))
    )
    (net (code "105") (name "Net-(T2-D)") (class "Default")
      (node (ref "LEDR2") (pin "1") (pinfunction "1_1") (pintype "passive"))
      (node (ref "T2") (pin "3") (pinfunction "D_3") (pintype "output"))
    )
    (net (code "106") (name "Net-(T3-D)") (class "Default")
      (node (ref "LEDY1") (pin "1") (pinfunction "1_1") (pintype "passive"))
      (node (ref "T3") (pin "3") (pinfunction "D_3") (pintype "output"))
    )
    (net (code "107") (name "Net-(T4-D)") (class "Default")
      (node (ref "LEDY2") (pin "1") (pinfunction "1_1") (pintype "passive"))
      (node (ref "T4") (pin "3") (pinfunction "D_3") (pintype "output"))
    )
    (net (code "108") (name "unconnected-(IC101-NC0-Pad2)") (class "Default")
      (node (ref "IC101") (pin "2") (pinfunction "NC0_2") (pintype "bidirectional"))
    )
    (net (code "109") (name "unconnected-(IC101-NC1-Pad6)") (class "Default")
      (node (ref "IC101") (pin "6") (pinfunction "NC1_6") (pintype "bidirectional"))
    )
    (net (code "110") (name "unconnected-(IC101-NC2-Pad7)") (class "Default")
      (node (ref "IC101") (pin "7") (pinfunction "NC2_7") (pintype "bidirectional"))
    )
  )
)
